# ATmega328p_Double_Sided_Example.net
KiCad netlist of a schematic drawn in EAGLE
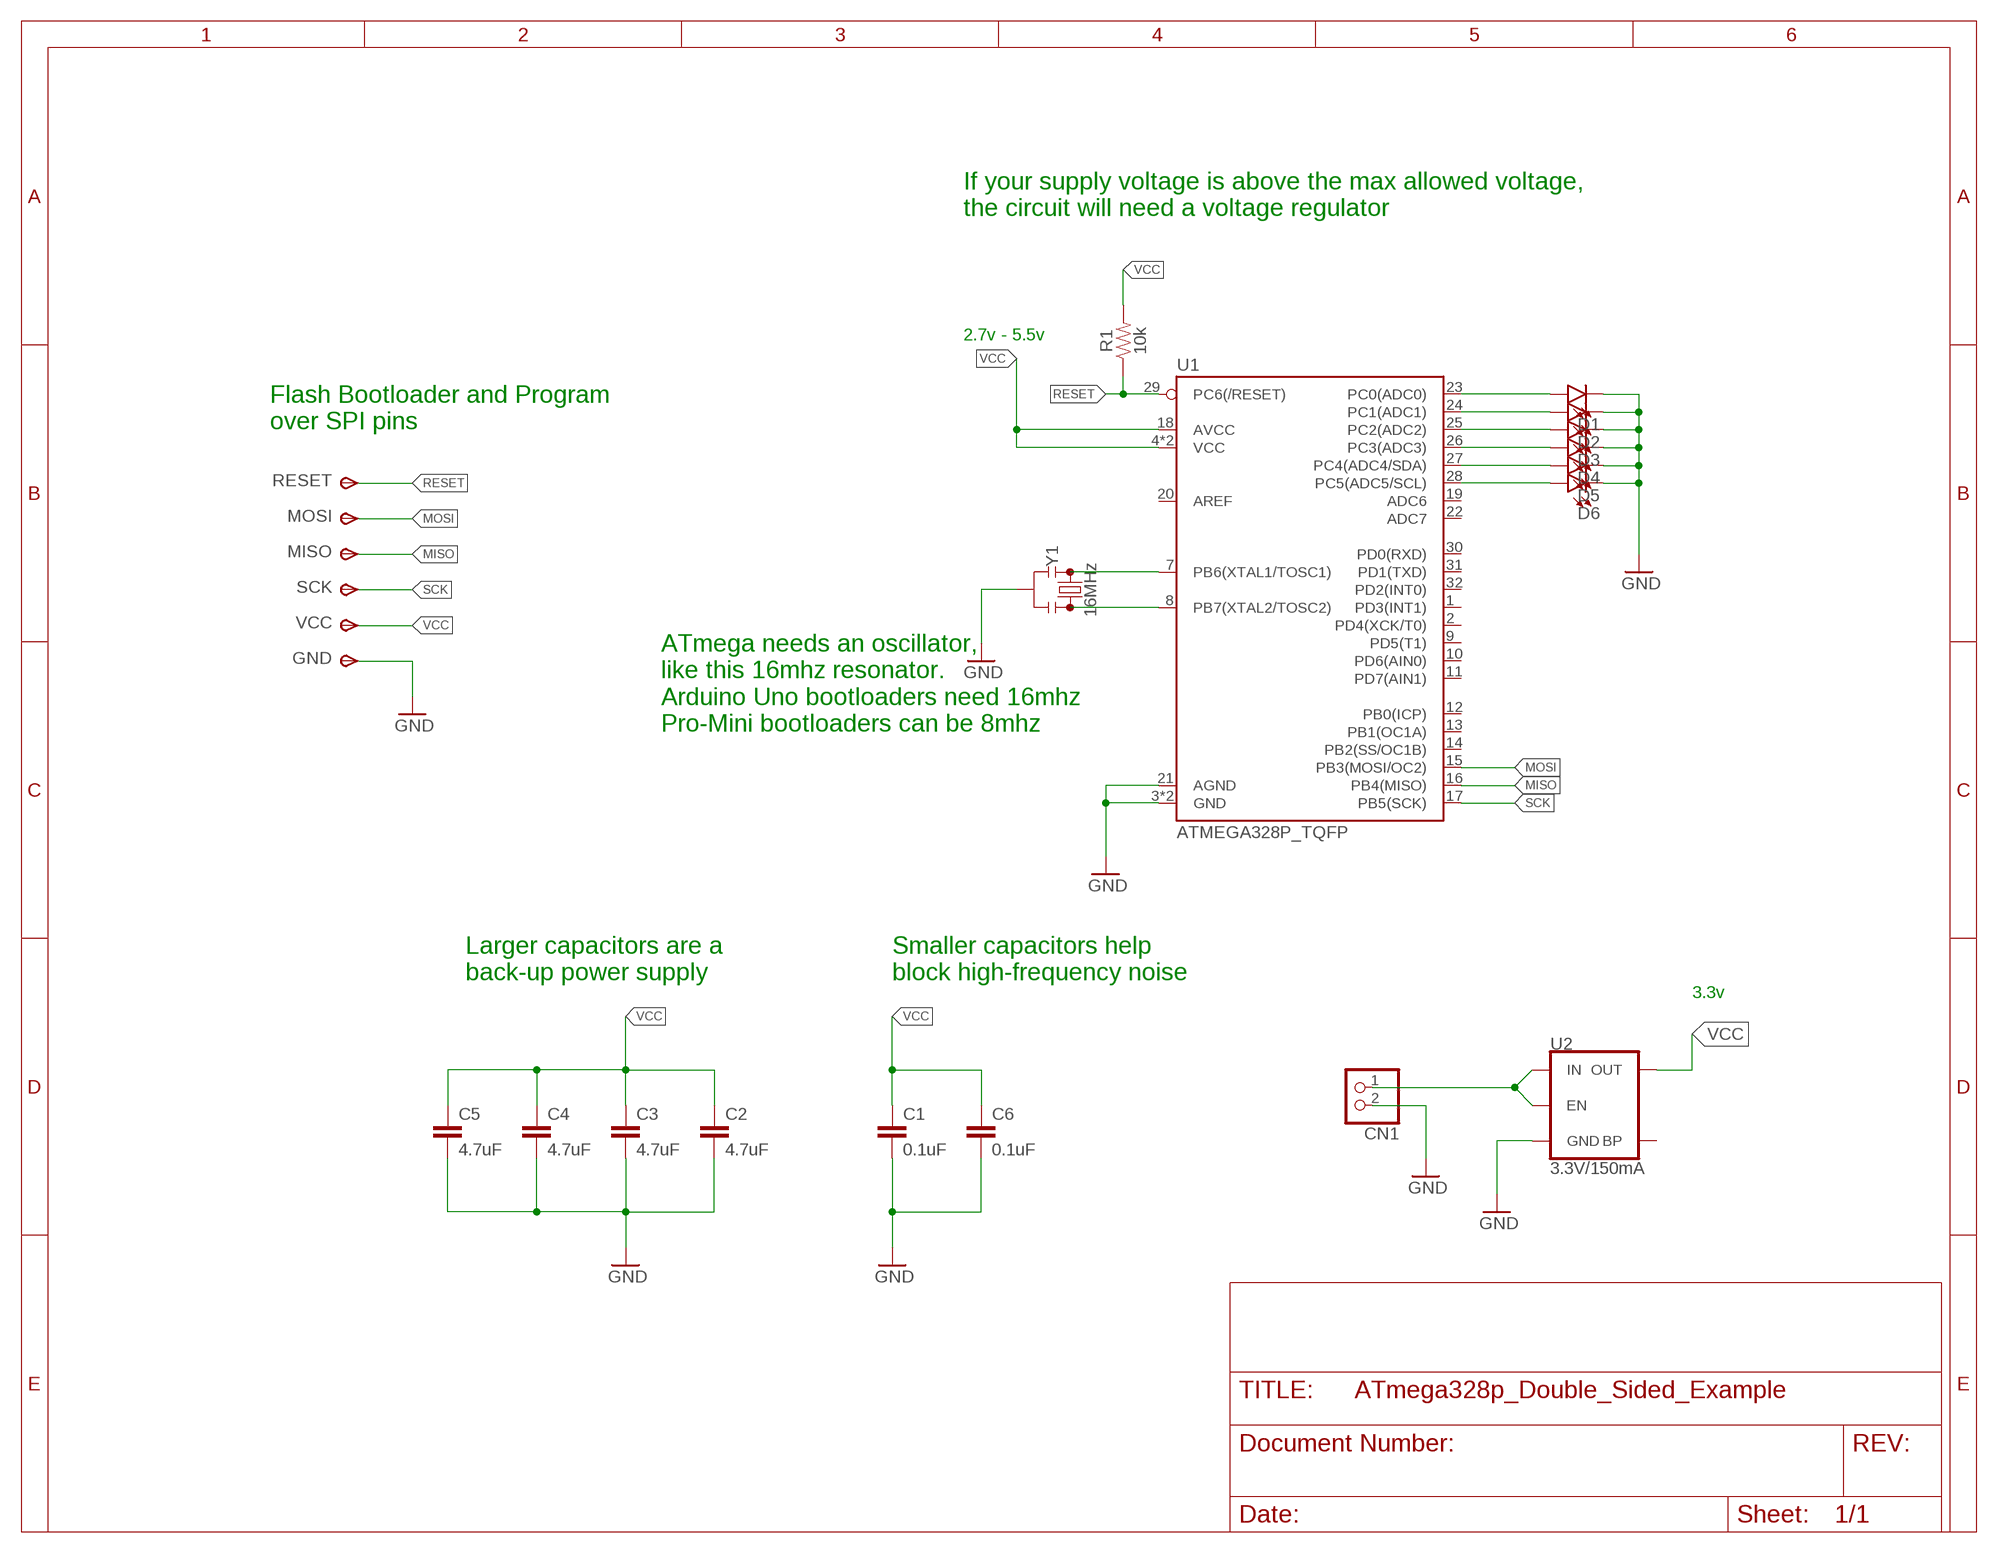
[diagram p0: schematic, sheet 1]

(export (version "E")
  (design (tool "Eeschema 10.0.6"))
  (components
    (comp (ref "C1")
      (value "0.1uF")
      (footprint "eagle-import:0603")
      (libsource (lib "eagle-import") (part "0.1UF-0603-25V-5%"))
    )
    (comp (ref "C2")
      (value "4.7uF")
      (footprint "eagle-import:0603")
      (libsource (lib "eagle-import") (part "4.7UF0603"))
    )
    (comp (ref "C3")
      (value "4.7uF")
      (footprint "eagle-import:0603")
      (libsource (lib "eagle-import") (part "4.7UF0603"))
    )
    (comp (ref "C4")
      (value "4.7uF")
      (footprint "eagle-import:0603")
      (libsource (lib "eagle-import") (part "4.7UF0603"))
    )
    (comp (ref "C5")
      (value "4.7uF")
      (footprint "eagle-import:0603")
      (libsource (lib "eagle-import") (part "4.7UF0603"))
    )
    (comp (ref "C6")
      (value "0.1uF")
      (footprint "eagle-import:0603")
      (libsource (lib "eagle-import") (part "0.1UF-0603-25V-5%"))
    )
    (comp (ref "CN1")
      (value "JST_2PIN-SMT-RA")
      (footprint "eagle-import:JST-PH-2-SMT-RA")
      (libsource (lib "eagle-import") (part "JST_2PIN-SMT-RA"))
    )
    (comp (ref "D1")
      (value "LED0603")
      (footprint "eagle-import:LED-0603")
      (libsource (lib "eagle-import") (part "LED0603"))
    )
    (comp (ref "D2")
      (value "LED0603")
      (footprint "eagle-import:LED-0603")
      (libsource (lib "eagle-import") (part "LED0603"))
    )
    (comp (ref "D3")
      (value "LED0603")
      (footprint "eagle-import:LED-0603")
      (libsource (lib "eagle-import") (part "LED0603"))
    )
    (comp (ref "D4")
      (value "LED0603")
      (footprint "eagle-import:LED-0603")
      (libsource (lib "eagle-import") (part "LED0603"))
    )
    (comp (ref "D5")
      (value "LED0603")
      (footprint "eagle-import:LED-0603")
      (libsource (lib "eagle-import") (part "LED0603"))
    )
    (comp (ref "D6")
      (value "LED0603")
      (footprint "eagle-import:LED-0603")
      (libsource (lib "eagle-import") (part "LED0603"))
    )
    (comp (ref "GND")
      (value "TPSTP14SQ")
      (footprint "eagle-import:TP14SQ")
      (libsource (lib "eagle-import") (part "TPSTP14SQ"))
    )
    (comp (ref "MISO")
      (value "TPSTP14SQ")
      (footprint "eagle-import:TP14SQ")
      (libsource (lib "eagle-import") (part "TPSTP14SQ"))
    )
    (comp (ref "MOSI")
      (value "TPSTP14SQ")
      (footprint "eagle-import:TP14SQ")
      (libsource (lib "eagle-import") (part "TPSTP14SQ"))
    )
    (comp (ref "R1")
      (value "10k")
      (footprint "eagle-import:0603")
      (libsource (lib "eagle-import") (part "10KOHM-0603-1/10W-1%"))
    )
    (comp (ref "RESET")
      (value "TPSTP14SQ")
      (footprint "eagle-import:TP14SQ")
      (libsource (lib "eagle-import") (part "TPSTP14SQ"))
    )
    (comp (ref "SCK")
      (value "TPSTP14SQ")
      (footprint "eagle-import:TP14SQ")
      (libsource (lib "eagle-import") (part "TPSTP14SQ"))
    )
    (comp (ref "U1")
      (value "ATMEGA328P_TQFP")
      (footprint "eagle-import:TQFP32-08")
      (libsource (lib "eagle-import") (part "ATMEGA328P_TQFP"))
    )
    (comp (ref "U2")
      (value "3.3V/150mA")
      (footprint "eagle-import:SOT23-5")
      (libsource (lib "eagle-import") (part "V_REG_MIC52053.3V"))
    )
    (comp (ref "VCC")
      (value "TPSTP14SQ")
      (footprint "eagle-import:TP14SQ")
      (libsource (lib "eagle-import") (part "TPSTP14SQ"))
    )
    (comp (ref "Y1")
      (value "16MHz")
      (footprint "eagle-import:RESONATOR-SMD-3.2X1.3")
      (libsource (lib "eagle-import") (part "RESONATOR-16MHZSMD_3.2X1.3"))
    )
  )
  (nets
    (net (code "1") (name "GND") (class "Default")
      (node (ref "C1") (pin "2") (pinfunction "2_2") (pintype "passive"))
      (node (ref "C2") (pin "2") (pinfunction "2_2") (pintype "passive"))
      (node (ref "C3") (pin "2") (pinfunction "2_2") (pintype "passive"))
      (node (ref "C4") (pin "2") (pinfunction "2_2") (pintype "passive"))
      (node (ref "C5") (pin "2") (pinfunction "2_2") (pintype "passive"))
      (node (ref "C6") (pin "2") (pinfunction "2_2") (pintype "passive"))
      (node (ref "CN1") (pin "2") (pinfunction "1_2") (pintype "passive"))
      (node (ref "D1") (pin "C") (pinfunction "C_C") (pintype "passive"))
      (node (ref "D2") (pin "C") (pinfunction "C_C") (pintype "passive"))
      (node (ref "D3") (pin "C") (pinfunction "C_C") (pintype "passive"))
      (node (ref "D4") (pin "C") (pinfunction "C_C") (pintype "passive"))
      (node (ref "D5") (pin "C") (pinfunction "C_C") (pintype "passive"))
      (node (ref "D6") (pin "C") (pinfunction "C_C") (pintype "passive"))
      (node (ref "GND") (pin "TP") (pinfunction "PP_TP") (pintype "input"))
      (node (ref "U1") (pin "21") (pinfunction "AGND_21") (pintype "bidirectional"))
      (node (ref "U1") (pin "3") (pinfunction "GND_3") (pintype "bidirectional"))
      (node (ref "U1") (pin "5") (pinfunction "GND_5") (pintype "bidirectional"))
      (node (ref "U2") (pin "2") (pinfunction "GND_2") (pintype "input"))
      (node (ref "Y1") (pin "2") (pinfunction "2_2") (pintype "passive"))
    )
    (net (code "2") (name "MISO") (class "Default")
      (node (ref "MISO") (pin "TP") (pinfunction "PP_TP") (pintype "input"))
      (node (ref "U1") (pin "16") (pinfunction "PB4(MISO)_16") (pintype "bidirectional"))
    )
    (net (code "3") (name "MOSI") (class "Default")
      (node (ref "MOSI") (pin "TP") (pinfunction "PP_TP") (pintype "input"))
      (node (ref "U1") (pin "15") (pinfunction "PB3(MOSI/OC2)_15") (pintype "bidirectional"))
    )
    (net (code "4") (name "Net-(CN1-2)") (class "Default")
      (node (ref "CN1") (pin "1") (pinfunction "2_1") (pintype "passive"))
      (node (ref "U2") (pin "1") (pinfunction "IN_1") (pintype "input"))
      (node (ref "U2") (pin "3") (pinfunction "EN_3") (pintype "input"))
    )
    (net (code "5") (name "Net-(U1-PB6(XTAL1{slash}TOSC1))") (class "Default")
      (node (ref "U1") (pin "7") (pinfunction "PB6(XTAL1/TOSC1)_7") (pintype "bidirectional"))
      (node (ref "Y1") (pin "1") (pinfunction "1_1") (pintype "passive"))
    )
    (net (code "6") (name "Net-(U1-PB7(XTAL2{slash}TOSC2))") (class "Default")
      (node (ref "U1") (pin "8") (pinfunction "PB7(XTAL2/TOSC2)_8") (pintype "bidirectional"))
      (node (ref "Y1") (pin "3") (pinfunction "3_3") (pintype "passive"))
    )
    (net (code "7") (name "Net-(U1-PC0(ADC0))") (class "Default")
      (node (ref "D1") (pin "A") (pinfunction "A_A") (pintype "passive"))
      (node (ref "U1") (pin "23") (pinfunction "PC0(ADC0)_23") (pintype "bidirectional"))
    )
    (net (code "8") (name "Net-(U1-PC1(ADC1))") (class "Default")
      (node (ref "D2") (pin "A") (pinfunction "A_A") (pintype "passive"))
      (node (ref "U1") (pin "24") (pinfunction "PC1(ADC1)_24") (pintype "bidirectional"))
    )
    (net (code "9") (name "Net-(U1-PC2(ADC2))") (class "Default")
      (node (ref "D3") (pin "A") (pinfunction "A_A") (pintype "passive"))
      (node (ref "U1") (pin "25") (pinfunction "PC2(ADC2)_25") (pintype "bidirectional"))
    )
    (net (code "10") (name "Net-(U1-PC3(ADC3))") (class "Default")
      (node (ref "D4") (pin "A") (pinfunction "A_A") (pintype "passive"))
      (node (ref "U1") (pin "26") (pinfunction "PC3(ADC3)_26") (pintype "bidirectional"))
    )
    (net (code "11") (name "Net-(U1-PC4(ADC4{slash}SDA))") (class "Default")
      (node (ref "D5") (pin "A") (pinfunction "A_A") (pintype "passive"))
      (node (ref "U1") (pin "27") (pinfunction "PC4(ADC4/SDA)_27") (pintype "bidirectional"))
    )
    (net (code "12") (name "Net-(U1-PC5(ADC5{slash}SCL))") (class "Default")
      (node (ref "D6") (pin "A") (pinfunction "A_A") (pintype "passive"))
      (node (ref "U1") (pin "28") (pinfunction "PC5(ADC5/SCL)_28") (pintype "bidirectional"))
    )
    (net (code "13") (name "RESET") (class "Default")
      (node (ref "R1") (pin "1") (pinfunction "1_1") (pintype "passive"))
      (node (ref "RESET") (pin "TP") (pinfunction "PP_TP") (pintype "input"))
      (node (ref "U1") (pin "29") (pinfunction "PC6(/RESET)_29") (pintype "bidirectional"))
    )
    (net (code "14") (name "SCK") (class "Default")
      (node (ref "SCK") (pin "TP") (pinfunction "PP_TP") (pintype "input"))
      (node (ref "U1") (pin "17") (pinfunction "PB5(SCK)_17") (pintype "bidirectional"))
    )
    (net (code "15") (name "VCC") (class "Default")
      (node (ref "C1") (pin "1") (pinfunction "1_1") (pintype "passive"))
      (node (ref "C2") (pin "1") (pinfunction "1_1") (pintype "passive"))
      (node (ref "C3") (pin "1") (pinfunction "1_1") (pintype "passive"))
      (node (ref "C4") (pin "1") (pinfunction "1_1") (pintype "passive"))
      (node (ref "C5") (pin "1") (pinfunction "1_1") (pintype "passive"))
      (node (ref "C6") (pin "1") (pinfunction "1_1") (pintype "passive"))
      (node (ref "R1") (pin "2") (pinfunction "2_2") (pintype "passive"))
      (node (ref "U1") (pin "18") (pinfunction "AVCC_18") (pintype "bidirectional"))
      (node (ref "U1") (pin "4") (pinfunction "VCC_4") (pintype "bidirectional"))
      (node (ref "U1") (pin "6") (pinfunction "VCC_6") (pintype "bidirectional"))
      (node (ref "U2") (pin "5") (pinfunction "OUT_5") (pintype "passive"))
      (node (ref "VCC") (pin "TP") (pinfunction "PP_TP") (pintype "input"))
    )
    (net (code "16") (name "unconnected-(U1-ADC6-Pad19)") (class "Default")
      (node (ref "U1") (pin "19") (pinfunction "ADC6_19") (pintype "bidirectional"))
    )
    (net (code "17") (name "unconnected-(U1-ADC7-Pad22)") (class "Default")
      (node (ref "U1") (pin "22") (pinfunction "ADC7_22") (pintype "bidirectional"))
    )
    (net (code "18") (name "unconnected-(U1-AREF-Pad20)") (class "Default")
      (node (ref "U1") (pin "20") (pinfunction "AREF_20") (pintype "bidirectional"))
    )
    (net (code "19") (name "unconnected-(U1-PB0(ICP)-Pad12)") (class "Default")
      (node (ref "U1") (pin "12") (pinfunction "PB0(ICP)_12") (pintype "bidirectional"))
    )
    (net (code "20") (name "unconnected-(U1-PB1(OC1A)-Pad13)") (class "Default")
      (node (ref "U1") (pin "13") (pinfunction "PB1(OC1A)_13") (pintype "bidirectional"))
    )
    (net (code "21") (name "unconnected-(U1-PB2(SS{slash}OC1B)-Pad14)") (class "Default")
      (node (ref "U1") (pin "14") (pinfunction "PB2(SS/OC1B)_14") (pintype "bidirectional"))
    )
    (net (code "22") (name "unconnected-(U1-PD0(RXD)-Pad30)") (class "Default")
      (node (ref "U1") (pin "30") (pinfunction "PD0(RXD)_30") (pintype "bidirectional"))
    )
    (net (code "23") (name "unconnected-(U1-PD1(TXD)-Pad31)") (class "Default")
      (node (ref "U1") (pin "31") (pinfunction "PD1(TXD)_31") (pintype "bidirectional"))
    )
    (net (code "24") (name "unconnected-(U1-PD2(INT0)-Pad32)") (class "Default")
      (node (ref "U1") (pin "32") (pinfunction "PD2(INT0)_32") (pintype "bidirectional"))
    )
    (net (code "25") (name "unconnected-(U1-PD3(INT1)-Pad1)") (class "Default")
      (node (ref "U1") (pin "1") (pinfunction "PD3(INT1)_1") (pintype "bidirectional"))
    )
    (net (code "26") (name "unconnected-(U1-PD4(XCK{slash}T0)-Pad2)") (class "Default")
      (node (ref "U1") (pin "2") (pinfunction "PD4(XCK/T0)_2") (pintype "bidirectional"))
    )
    (net (code "27") (name "unconnected-(U1-PD5(T1)-Pad9)") (class "Default")
      (node (ref "U1") (pin "9") (pinfunction "PD5(T1)_9") (pintype "bidirectional"))
    )
    (net (code "28") (name "unconnected-(U1-PD6(AIN0)-Pad10)") (class "Default")
      (node (ref "U1") (pin "10") (pinfunction "PD6(AIN0)_10") (pintype "bidirectional"))
    )
    (net (code "29") (name "unconnected-(U1-PD7(AIN1)-Pad11)") (class "Default")
      (node (ref "U1") (pin "11") (pinfunction "PD7(AIN1)_11") (pintype "bidirectional"))
    )
    (net (code "30") (name "unconnected-(U2-BP-Pad4)") (class "Default")
      (node (ref "U2") (pin "4") (pinfunction "BP_4") (pintype "input"))
    )
  )
)
